# ProtocolAnalyzer.net
KiCad netlist of a schematic drawn in Altium Designer
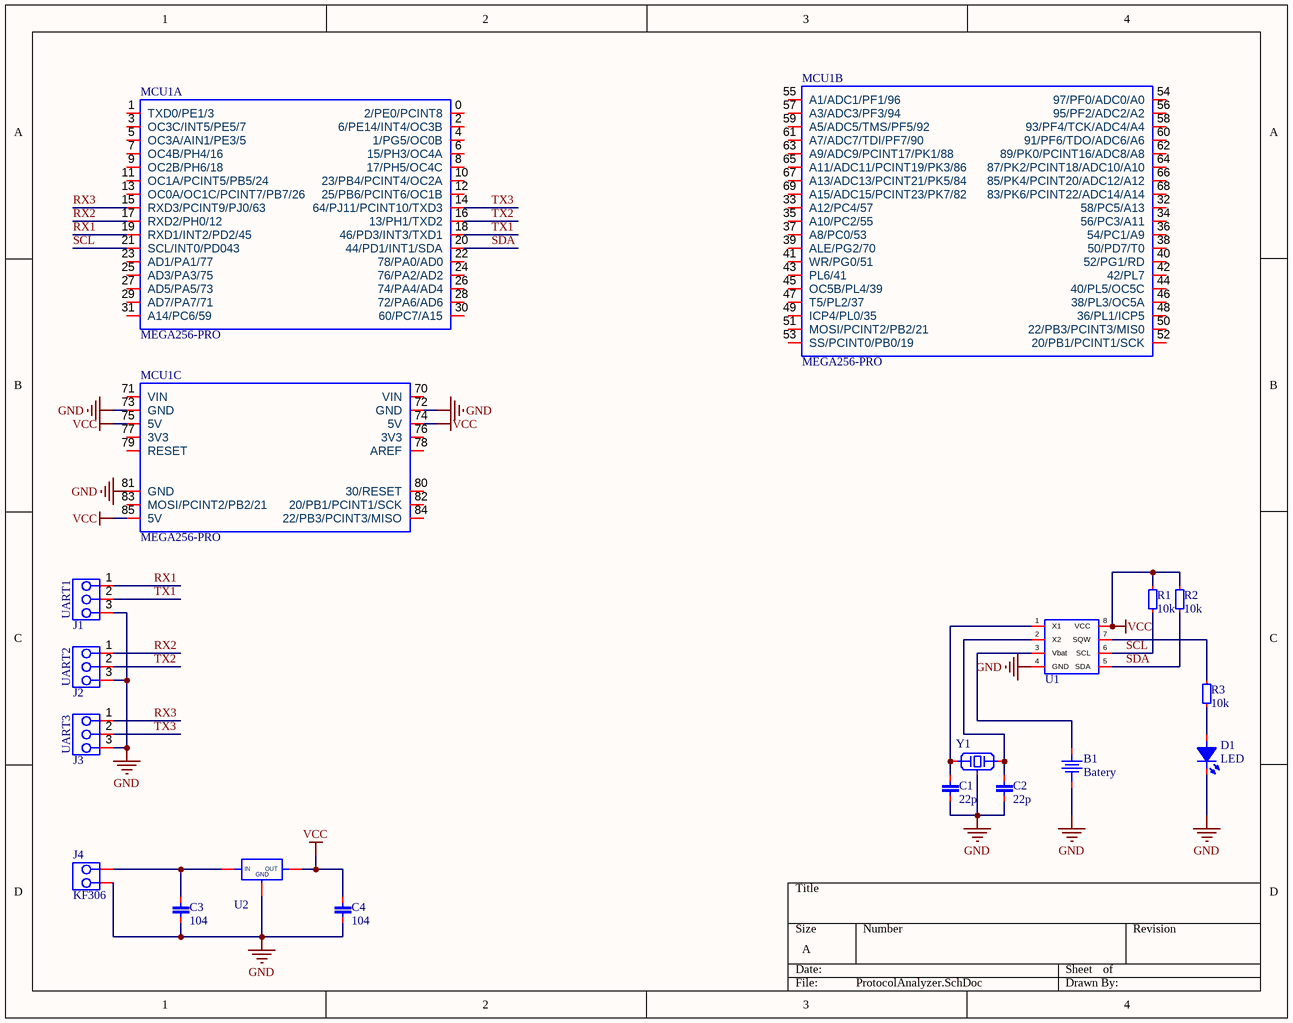
[diagram p0: ProtocolAnalyzer.SchDoc]

(export (version "E")
  (design (tool "Eeschema 10.0.6"))
  (components
    (comp (ref "B1")
      (value "Batery")
      (footprint "CR1220")
      (libsource (lib "MyAltiumLibrary") (part "Batery"))
    )
    (comp (ref "C1")
      (value "22p")
      (footprint "C0805")
      (libsource (lib "MyAltiumLibrary") (part "Capacitors(SMD)"))
    )
    (comp (ref "C2")
      (value "22p")
      (footprint "C0805")
      (libsource (lib "MyAltiumLibrary") (part "Capacitors(SMD)"))
    )
    (comp (ref "C3") (value "104") (footprint "C1206") (libsource (lib "") (part "Capacitors(SMD)_1")))
    (comp (ref "C4") (value "104") (footprint "C1206") (libsource (lib "") (part "Capacitors(SMD)_1")))
    (comp (ref "D1")
      (value "LED")
      (footprint "L0805RED")
      (libsource (lib "MyAltiumLibrary") (part "LED0805"))
    )
    (comp (ref "J1")
      (value "UART1")
      (footprint "JST - XH - Thru (R) - 3Pin - 2.54mm")
      (libsource (lib "MyAltiumLibrary") (part "JST - XH - Thru (R) - 3Pin - 2.54mm"))
    )
    (comp (ref "J2")
      (value "UART2")
      (footprint "JST - XH - Thru (R) - 3Pin - 2.54mm")
      (libsource (lib "MyAltiumLibrary") (part "JST - XH - Thru (R) - 3Pin - 2.54mm"))
    )
    (comp (ref "J3")
      (value "UART3")
      (footprint "JST - XH - Thru (R) - 3Pin - 2.54mm")
      (libsource (lib "MyAltiumLibrary") (part "JST - XH - Thru (R) - 3Pin - 2.54mm"))
    )
    (comp (ref "J4")
      (value "KF306")
      (footprint "DG306-5.0-02P-12-00AH")
      (libsource (lib "MyAltiumLibrary") (part "DG306-5.0-02P-12-00AH"))
    )
    (comp (ref "MCU1")
      (value "MEGA256-PRO")
      (footprint "MEGA2560-PRO")
      (libsource (lib "MyAltiumLibrary") (part "Arduino Mega 2560 Pro"))
    )
    (comp (ref "R1")
      (value "10k")
      (footprint "R0805")
      (libsource (lib "MyAltiumLibrary") (part "Resistors-SMD"))
    )
    (comp (ref "R2")
      (value "10k")
      (footprint "R0805")
      (libsource (lib "MyAltiumLibrary") (part "Resistors-SMD"))
    )
    (comp (ref "R3")
      (value "10k")
      (footprint "R0805")
      (libsource (lib "MyAltiumLibrary") (part "Resistors-SMD"))
    )
    (comp (ref "U1")
      (value "RealTime")
      (footprint "SOIC08_1.27_6.0")
      (libsource (lib "MyAltiumLibrary") (part "RealTime-DS1307"))
    )
    (comp (ref "U2")
      (value "LM7805")
      (footprint "TO252-3")
      (libsource (lib "MyAltiumLibrary") (part "Ic-LM7805"))
    )
    (comp (ref "Y1")
      (value "32.768KHz")
      (footprint "DT-26")
      (libsource (lib "MyAltiumLibrary") (part "Crystal 32.768KHz"))
    )
  )
  (nets
    (net (code "1") (name "/RX1") (class "Default")
      (node (ref "J1") (pin "1") (pinfunction "1_1") (pintype "passive"))
      (node (ref "MCU1") (pin "19") (pinfunction "RXD1/INT2/PD2/45_19") (pintype "passive"))
    )
    (net (code "2") (name "/RX2") (class "Default")
      (node (ref "J2") (pin "1") (pinfunction "1_1") (pintype "passive"))
      (node (ref "MCU1") (pin "17") (pinfunction "RXD2/PH0/12_17") (pintype "passive"))
    )
    (net (code "3") (name "/RX3") (class "Default")
      (node (ref "J3") (pin "1") (pinfunction "1_1") (pintype "passive"))
      (node (ref "MCU1") (pin "15") (pinfunction "RXD3/PCINT9/PJ0/63_15") (pintype "passive"))
    )
    (net (code "4") (name "/SCL") (class "Default")
      (node (ref "MCU1") (pin "21") (pinfunction "SCL/INT0/PD043_21") (pintype "passive"))
      (node (ref "R1") (pin "1") (pinfunction "1_1") (pintype "passive"))
      (node (ref "U1") (pin "6") (pinfunction "SCL_6") (pintype "passive"))
    )
    (net (code "5") (name "/SDA") (class "Default")
      (node (ref "MCU1") (pin "20") (pinfunction "44/PD1/INT1/SDA_20") (pintype "passive"))
      (node (ref "R2") (pin "1") (pinfunction "1_1") (pintype "passive"))
      (node (ref "U1") (pin "5") (pinfunction "SDA_5") (pintype "passive"))
    )
    (net (code "6") (name "/TX1") (class "Default")
      (node (ref "J1") (pin "2") (pinfunction "2_2") (pintype "passive"))
      (node (ref "MCU1") (pin "18") (pinfunction "46/PD3/INT3/TXD1_18") (pintype "passive"))
    )
    (net (code "7") (name "/TX2") (class "Default")
      (node (ref "J2") (pin "2") (pinfunction "2_2") (pintype "passive"))
      (node (ref "MCU1") (pin "16") (pinfunction "13/PH1/TXD2_16") (pintype "passive"))
    )
    (net (code "8") (name "/TX3") (class "Default")
      (node (ref "J3") (pin "2") (pinfunction "2_2") (pintype "passive"))
      (node (ref "MCU1") (pin "14") (pinfunction "64/PJ11/PCINT10/TXD3_14") (pintype "passive"))
    )
    (net (code "9") (name "GND") (class "Default")
      (node (ref "B1") (pin "2") (pinfunction "2_2") (pintype "passive"))
      (node (ref "C1") (pin "1") (pinfunction "1_1") (pintype "passive"))
      (node (ref "C2") (pin "1") (pinfunction "1_1") (pintype "passive"))
      (node (ref "C3") (pin "2") (pinfunction "2_2") (pintype "passive"))
      (node (ref "C4") (pin "2") (pinfunction "2_2") (pintype "passive"))
      (node (ref "D1") (pin "2") (pinfunction "K_2") (pintype "passive"))
      (node (ref "J1") (pin "3") (pinfunction "3_3") (pintype "passive"))
      (node (ref "J2") (pin "3") (pinfunction "3_3") (pintype "passive"))
      (node (ref "J3") (pin "3") (pinfunction "3_3") (pintype "passive"))
      (node (ref "J4") (pin "2") (pinfunction "2_2") (pintype "passive"))
      (node (ref "MCU1") (pin "72") (pinfunction "GND_72") (pintype "passive"))
      (node (ref "MCU1") (pin "73") (pinfunction "GND_73") (pintype "passive"))
      (node (ref "MCU1") (pin "81") (pinfunction "GND_81") (pintype "passive"))
      (node (ref "U1") (pin "4") (pinfunction "GND_4") (pintype "passive"))
      (node (ref "U2") (pin "2") (pinfunction "GND_2") (pintype "passive"))
      (node (ref "Y1") (pin "3") (pinfunction "GND_3") (pintype "passive"))
    )
    (net (code "10") (name "Net-(D1-A)") (class "Default")
      (node (ref "D1") (pin "1") (pinfunction "A_1") (pintype "passive"))
      (node (ref "R3") (pin "1") (pinfunction "1_1") (pintype "passive"))
    )
    (net (code "11") (name "Net-(U1-SQW)") (class "Default")
      (node (ref "R3") (pin "2") (pinfunction "2_2") (pintype "passive"))
      (node (ref "U1") (pin "7") (pinfunction "SQW_7") (pintype "passive"))
    )
    (net (code "12") (name "Net-(U1-Vbat)") (class "Default")
      (node (ref "B1") (pin "1") (pinfunction "1_1") (pintype "passive"))
      (node (ref "U1") (pin "3") (pinfunction "Vbat_3") (pintype "passive"))
    )
    (net (code "13") (name "Net-(U1-X1)") (class "Default")
      (node (ref "C1") (pin "2") (pinfunction "2_2") (pintype "passive"))
      (node (ref "U1") (pin "1") (pinfunction "X1_1") (pintype "passive"))
      (node (ref "Y1") (pin "2") (pinfunction "2_2") (pintype "passive"))
    )
    (net (code "14") (name "Net-(U1-X2)") (class "Default")
      (node (ref "C2") (pin "2") (pinfunction "2_2") (pintype "passive"))
      (node (ref "U1") (pin "2") (pinfunction "X2_2") (pintype "passive"))
      (node (ref "Y1") (pin "1") (pinfunction "1_1") (pintype "passive"))
    )
    (net (code "15") (name "Net-(U2-IN)") (class "Default")
      (node (ref "C3") (pin "1") (pinfunction "1_1") (pintype "passive"))
      (node (ref "J4") (pin "1") (pinfunction "1_1") (pintype "passive"))
      (node (ref "U2") (pin "1") (pinfunction "IN_1") (pintype "passive"))
    )
    (net (code "16") (name "VCC") (class "Default")
      (node (ref "C4") (pin "1") (pinfunction "1_1") (pintype "passive"))
      (node (ref "MCU1") (pin "74") (pinfunction "5V_74") (pintype "passive"))
      (node (ref "MCU1") (pin "75") (pinfunction "5V_75") (pintype "passive"))
      (node (ref "MCU1") (pin "85") (pinfunction "5V_85") (pintype "passive"))
      (node (ref "R1") (pin "2") (pinfunction "2_2") (pintype "passive"))
      (node (ref "R2") (pin "2") (pinfunction "2_2") (pintype "passive"))
      (node (ref "U1") (pin "8") (pinfunction "VCC_8") (pintype "passive"))
      (node (ref "U2") (pin "3") (pinfunction "OUT_3") (pintype "passive"))
    )
    (net (code "17") (name "unconnected-(MCU1A-1{slash}PG5{slash}OC0B-Pad4)") (class "Default")
      (node (ref "MCU1") (pin "4") (pinfunction "1/PG5/OC0B_4") (pintype "passive"))
    )
    (net (code "18") (name "unconnected-(MCU1A-2{slash}PE0{slash}PCINT8-Pad0)") (class "Default")
      (node (ref "MCU1") (pin "0") (pinfunction "2/PE0/PCINT8_0") (pintype "passive"))
    )
    (net (code "19") (name "unconnected-(MCU1A-6{slash}PE14{slash}INT4{slash}OC3B-Pad2)") (class "Default")
      (node (ref "MCU1") (pin "2") (pinfunction "6/PE14/INT4/OC3B_2") (pintype "passive"))
    )
    (net (code "20") (name "unconnected-(MCU1A-15{slash}PH3{slash}OC4A-Pad6)") (class "Default")
      (node (ref "MCU1") (pin "6") (pinfunction "15/PH3/OC4A_6") (pintype "passive"))
    )
    (net (code "21") (name "unconnected-(MCU1A-17{slash}PH5{slash}OC4C-Pad8)") (class "Default")
      (node (ref "MCU1") (pin "8") (pinfunction "17/PH5/OC4C_8") (pintype "passive"))
    )
    (net (code "22") (name "unconnected-(MCU1A-23{slash}PB4{slash}PCINT4{slash}OC2A-Pad10)") (class "Default")
      (node (ref "MCU1") (pin "10") (pinfunction "23/PB4/PCINT4/OC2A_10") (pintype "passive"))
    )
    (net (code "23") (name "unconnected-(MCU1A-25{slash}PB6{slash}PCINT6{slash}OC1B-Pad12)") (class "Default")
      (node (ref "MCU1") (pin "12") (pinfunction "25/PB6/PCINT6/OC1B_12") (pintype "passive"))
    )
    (net (code "24") (name "unconnected-(MCU1A-60{slash}PC7{slash}A15-Pad30)") (class "Default")
      (node (ref "MCU1") (pin "30") (pinfunction "60/PC7/A15_30") (pintype "passive"))
    )
    (net (code "25") (name "unconnected-(MCU1A-72{slash}PA6{slash}AD6-Pad28)") (class "Default")
      (node (ref "MCU1") (pin "28") (pinfunction "72/PA6/AD6_28") (pintype "passive"))
    )
    (net (code "26") (name "unconnected-(MCU1A-74{slash}PA4{slash}AD4-Pad26)") (class "Default")
      (node (ref "MCU1") (pin "26") (pinfunction "74/PA4/AD4_26") (pintype "passive"))
    )
    (net (code "27") (name "unconnected-(MCU1A-76{slash}PA2{slash}AD2-Pad24)") (class "Default")
      (node (ref "MCU1") (pin "24") (pinfunction "76/PA2/AD2_24") (pintype "passive"))
    )
    (net (code "28") (name "unconnected-(MCU1A-78{slash}PA0{slash}AD0-Pad22)") (class "Default")
      (node (ref "MCU1") (pin "22") (pinfunction "78/PA0/AD0_22") (pintype "passive"))
    )
    (net (code "29") (name "unconnected-(MCU1A-A14{slash}PC6{slash}59-Pad31)") (class "Default")
      (node (ref "MCU1") (pin "31") (pinfunction "A14/PC6/59_31") (pintype "passive"))
    )
    (net (code "30") (name "unconnected-(MCU1A-AD1{slash}PA1{slash}77-Pad23)") (class "Default")
      (node (ref "MCU1") (pin "23") (pinfunction "AD1/PA1/77_23") (pintype "passive"))
    )
    (net (code "31") (name "unconnected-(MCU1A-AD3{slash}PA3{slash}75-Pad25)") (class "Default")
      (node (ref "MCU1") (pin "25") (pinfunction "AD3/PA3/75_25") (pintype "passive"))
    )
    (net (code "32") (name "unconnected-(MCU1A-AD5{slash}PA5{slash}73-Pad27)") (class "Default")
      (node (ref "MCU1") (pin "27") (pinfunction "AD5/PA5/73_27") (pintype "passive"))
    )
    (net (code "33") (name "unconnected-(MCU1A-AD7{slash}PA7{slash}71-Pad29)") (class "Default")
      (node (ref "MCU1") (pin "29") (pinfunction "AD7/PA7/71_29") (pintype "passive"))
    )
    (net (code "34") (name "unconnected-(MCU1A-OC0A{slash}OC1C{slash}PCINT7{slash}PB7{slash}26-Pad13)") (class "Default")
      (node (ref "MCU1") (pin "13") (pinfunction "OC0A/OC1C/PCINT7/PB7/26_13") (pintype "passive"))
    )
    (net (code "35") (name "unconnected-(MCU1A-OC1A{slash}PCINT5{slash}PB5{slash}24-Pad11)") (class "Default")
      (node (ref "MCU1") (pin "11") (pinfunction "OC1A/PCINT5/PB5/24_11") (pintype "passive"))
    )
    (net (code "36") (name "unconnected-(MCU1A-OC2B{slash}PH6{slash}18-Pad9)") (class "Default")
      (node (ref "MCU1") (pin "9") (pinfunction "OC2B/PH6/18_9") (pintype "passive"))
    )
    (net (code "37") (name "unconnected-(MCU1A-OC3A{slash}AIN1{slash}PE3{slash}5-Pad5)") (class "Default")
      (node (ref "MCU1") (pin "5") (pinfunction "OC3A/AIN1/PE3/5_5") (pintype "passive"))
    )
    (net (code "38") (name "unconnected-(MCU1A-OC3C{slash}INT5{slash}PE5{slash}7-Pad3)") (class "Default")
      (node (ref "MCU1") (pin "3") (pinfunction "OC3C/INT5/PE5/7_3") (pintype "passive"))
    )
    (net (code "39") (name "unconnected-(MCU1A-OC4B{slash}PH4{slash}16-Pad7)") (class "Default")
      (node (ref "MCU1") (pin "7") (pinfunction "OC4B/PH4/16_7") (pintype "passive"))
    )
    (net (code "40") (name "unconnected-(MCU1A-TXD0{slash}PE1{slash}3-Pad1)") (class "Default")
      (node (ref "MCU1") (pin "1") (pinfunction "TXD0/PE1/3_1") (pintype "passive"))
    )
    (net (code "41") (name "unconnected-(MCU1B-20{slash}PB1{slash}PCINT1{slash}SCK-Pad52)") (class "Default")
      (node (ref "MCU1") (pin "52") (pinfunction "20/PB1/PCINT1/SCK_52") (pintype "passive"))
    )
    (net (code "42") (name "unconnected-(MCU1B-22{slash}PB3{slash}PCINT3{slash}MIS0-Pad50)") (class "Default")
      (node (ref "MCU1") (pin "50") (pinfunction "22/PB3/PCINT3/MIS0_50") (pintype "passive"))
    )
    (net (code "43") (name "unconnected-(MCU1B-36{slash}PL1{slash}ICP5-Pad48)") (class "Default")
      (node (ref "MCU1") (pin "48") (pinfunction "36/PL1/ICP5_48") (pintype "passive"))
    )
    (net (code "44") (name "unconnected-(MCU1B-38{slash}PL3{slash}OC5A-Pad46)") (class "Default")
      (node (ref "MCU1") (pin "46") (pinfunction "38/PL3/OC5A_46") (pintype "passive"))
    )
    (net (code "45") (name "unconnected-(MCU1B-40{slash}PL5{slash}OC5C-Pad44)") (class "Default")
      (node (ref "MCU1") (pin "44") (pinfunction "40/PL5/OC5C_44") (pintype "passive"))
    )
    (net (code "46") (name "unconnected-(MCU1B-42{slash}PL7-Pad42)") (class "Default")
      (node (ref "MCU1") (pin "42") (pinfunction "42/PL7_42") (pintype "passive"))
    )
    (net (code "47") (name "unconnected-(MCU1B-50{slash}PD7{slash}T0-Pad38)") (class "Default")
      (node (ref "MCU1") (pin "38") (pinfunction "50/PD7/T0_38") (pintype "passive"))
    )
    (net (code "48") (name "unconnected-(MCU1B-52{slash}PG1{slash}RD-Pad40)") (class "Default")
      (node (ref "MCU1") (pin "40") (pinfunction "52/PG1/RD_40") (pintype "passive"))
    )
    (net (code "49") (name "unconnected-(MCU1B-54{slash}PC1{slash}A9-Pad36)") (class "Default")
      (node (ref "MCU1") (pin "36") (pinfunction "54/PC1/A9_36") (pintype "passive"))
    )
    (net (code "50") (name "unconnected-(MCU1B-56{slash}PC3{slash}A11-Pad34)") (class "Default")
      (node (ref "MCU1") (pin "34") (pinfunction "56/PC3/A11_34") (pintype "passive"))
    )
    (net (code "51") (name "unconnected-(MCU1B-58{slash}PC5{slash}A13-Pad32)") (class "Default")
      (node (ref "MCU1") (pin "32") (pinfunction "58/PC5/A13_32") (pintype "passive"))
    )
    (net (code "52") (name "unconnected-(MCU1B-83{slash}PK6{slash}PCINT22{slash}ADC14{slash}A14-Pad68)") (class "Default")
      (node (ref "MCU1") (pin "68") (pinfunction "83/PK6/PCINT22/ADC14/A14_68") (pintype "passive"))
    )
    (net (code "53") (name "unconnected-(MCU1B-85{slash}PK4{slash}PCINT20{slash}ADC12{slash}A12-Pad66)") (class "Default")
      (node (ref "MCU1") (pin "66") (pinfunction "85/PK4/PCINT20/ADC12/A12_66") (pintype "passive"))
    )
    (net (code "54") (name "unconnected-(MCU1B-87{slash}PK2{slash}PCINT18{slash}ADC10{slash}A10-Pad64)") (class "Default")
      (node (ref "MCU1") (pin "64") (pinfunction "87/PK2/PCINT18/ADC10/A10_64") (pintype "passive"))
    )
    (net (code "55") (name "unconnected-(MCU1B-89{slash}PK0{slash}PCINT16{slash}ADC8{slash}A8-Pad62)") (class "Default")
      (node (ref "MCU1") (pin "62") (pinfunction "89/PK0/PCINT16/ADC8/A8_62") (pintype "passive"))
    )
    (net (code "56") (name "unconnected-(MCU1B-91{slash}PF6{slash}TDO{slash}ADC6{slash}A6-Pad60)") (class "Default")
      (node (ref "MCU1") (pin "60") (pinfunction "91/PF6/TDO/ADC6/A6_60") (pintype "passive"))
    )
    (net (code "57") (name "unconnected-(MCU1B-93{slash}PF4{slash}TCK{slash}ADC4{slash}A4-Pad58)") (class "Default")
      (node (ref "MCU1") (pin "58") (pinfunction "93/PF4/TCK/ADC4/A4_58") (pintype "passive"))
    )
    (net (code "58") (name "unconnected-(MCU1B-95{slash}PF2{slash}ADC2{slash}A2-Pad56)") (class "Default")
      (node (ref "MCU1") (pin "56") (pinfunction "95/PF2/ADC2/A2_56") (pintype "passive"))
    )
    (net (code "59") (name "unconnected-(MCU1B-97{slash}PF0{slash}ADC0{slash}A0-Pad54)") (class "Default")
      (node (ref "MCU1") (pin "54") (pinfunction "97/PF0/ADC0/A0_54") (pintype "passive"))
    )
    (net (code "60") (name "unconnected-(MCU1B-A1{slash}ADC1{slash}PF1{slash}96-Pad55)") (class "Default")
      (node (ref "MCU1") (pin "55") (pinfunction "A1/ADC1/PF1/96_55") (pintype "passive"))
    )
    (net (code "61") (name "unconnected-(MCU1B-A3{slash}ADC3{slash}PF3{slash}94-Pad57)") (class "Default")
      (node (ref "MCU1") (pin "57") (pinfunction "A3/ADC3/PF3/94_57") (pintype "passive"))
    )
    (net (code "62") (name "unconnected-(MCU1B-A5{slash}ADC5{slash}TMS{slash}PF5{slash}92-Pad59)") (class "Default")
      (node (ref "MCU1") (pin "59") (pinfunction "A5/ADC5/TMS/PF5/92_59") (pintype "passive"))
    )
    (net (code "63") (name "unconnected-(MCU1B-A7{slash}ADC7{slash}TDI{slash}PF7{slash}90-Pad61)") (class "Default")
      (node (ref "MCU1") (pin "61") (pinfunction "A7/ADC7/TDI/PF7/90_61") (pintype "passive"))
    )
    (net (code "64") (name "unconnected-(MCU1B-A8{slash}PC0{slash}53-Pad37)") (class "Default")
      (node (ref "MCU1") (pin "37") (pinfunction "A8/PC0/53_37") (pintype "passive"))
    )
    (net (code "65") (name "unconnected-(MCU1B-A9{slash}ADC9{slash}PCINT17{slash}PK1{slash}88-Pad63)") (class "Default")
      (node (ref "MCU1") (pin "63") (pinfunction "A9/ADC9/PCINT17/PK1/88_63") (pintype "passive"))
    )
    (net (code "66") (name "unconnected-(MCU1B-A10{slash}PC2{slash}55-Pad35)") (class "Default")
      (node (ref "MCU1") (pin "35") (pinfunction "A10/PC2/55_35") (pintype "passive"))
    )
    (net (code "67") (name "unconnected-(MCU1B-A11{slash}ADC11{slash}PCINT19{slash}PK3{slash}86-Pad65)") (class "Default")
      (node (ref "MCU1") (pin "65") (pinfunction "A11/ADC11/PCINT19/PK3/86_65") (pintype "passive"))
    )
    (net (code "68") (name "unconnected-(MCU1B-A12{slash}PC4{slash}57-Pad33)") (class "Default")
      (node (ref "MCU1") (pin "33") (pinfunction "A12/PC4/57_33") (pintype "passive"))
    )
    (net (code "69") (name "unconnected-(MCU1B-A13{slash}ADC13{slash}PCINT21{slash}PK5{slash}84-Pad67)") (class "Default")
      (node (ref "MCU1") (pin "67") (pinfunction "A13/ADC13/PCINT21/PK5/84_67") (pintype "passive"))
    )
    (net (code "70") (name "unconnected-(MCU1B-A15{slash}ADC15{slash}PCINT23{slash}PK7{slash}82-Pad69)") (class "Default")
      (node (ref "MCU1") (pin "69") (pinfunction "A15/ADC15/PCINT23/PK7/82_69") (pintype "passive"))
    )
    (net (code "71") (name "unconnected-(MCU1B-ALE{slash}PG2{slash}70-Pad39)") (class "Default")
      (node (ref "MCU1") (pin "39") (pinfunction "ALE/PG2/70_39") (pintype "passive"))
    )
    (net (code "72") (name "unconnected-(MCU1B-ICP4{slash}PL0{slash}35-Pad49)") (class "Default")
      (node (ref "MCU1") (pin "49") (pinfunction "ICP4/PL0/35_49") (pintype "passive"))
    )
    (net (code "73") (name "unconnected-(MCU1B-MOSI{slash}PCINT2{slash}PB2{slash}21-Pad51)") (class "Default")
      (node (ref "MCU1") (pin "51") (pinfunction "MOSI/PCINT2/PB2/21_51") (pintype "passive"))
    )
    (net (code "74") (name "unconnected-(MCU1B-OC5B{slash}PL4{slash}39-Pad45)") (class "Default")
      (node (ref "MCU1") (pin "45") (pinfunction "OC5B/PL4/39_45") (pintype "passive"))
    )
    (net (code "75") (name "unconnected-(MCU1B-PL6{slash}41-Pad43)") (class "Default")
      (node (ref "MCU1") (pin "43") (pinfunction "PL6/41_43") (pintype "passive"))
    )
    (net (code "76") (name "unconnected-(MCU1B-SS{slash}PCINT0{slash}PB0{slash}19-Pad53)") (class "Default")
      (node (ref "MCU1") (pin "53") (pinfunction "SS/PCINT0/PB0/19_53") (pintype "passive"))
    )
    (net (code "77") (name "unconnected-(MCU1B-T5{slash}PL2{slash}37-Pad47)") (class "Default")
      (node (ref "MCU1") (pin "47") (pinfunction "T5/PL2/37_47") (pintype "passive"))
    )
    (net (code "78") (name "unconnected-(MCU1B-WR{slash}PG0{slash}51-Pad41)") (class "Default")
      (node (ref "MCU1") (pin "41") (pinfunction "WR/PG0/51_41") (pintype "passive"))
    )
    (net (code "79") (name "unconnected-(MCU1C-3V3-Pad76)") (class "Default")
      (node (ref "MCU1") (pin "76") (pinfunction "3V3_76") (pintype "passive"))
    )
    (net (code "80") (name "unconnected-(MCU1C-3V3-Pad77)") (class "Default")
      (node (ref "MCU1") (pin "77") (pinfunction "3V3_77") (pintype "passive"))
    )
    (net (code "81") (name "unconnected-(MCU1C-20{slash}PB1{slash}PCINT1{slash}SCK-Pad82)") (class "Default")
      (node (ref "MCU1") (pin "82") (pinfunction "20/PB1/PCINT1/SCK_82") (pintype "passive"))
    )
    (net (code "82") (name "unconnected-(MCU1C-22{slash}PB3{slash}PCINT3{slash}MISO-Pad84)") (class "Default")
      (node (ref "MCU1") (pin "84") (pinfunction "22/PB3/PCINT3/MISO_84") (pintype "passive"))
    )
    (net (code "83") (name "unconnected-(MCU1C-30{slash}RESET-Pad80)") (class "Default")
      (node (ref "MCU1") (pin "80") (pinfunction "30/RESET_80") (pintype "passive"))
    )
    (net (code "84") (name "unconnected-(MCU1C-AREF-Pad78)") (class "Default")
      (node (ref "MCU1") (pin "78") (pinfunction "AREF_78") (pintype "passive"))
    )
    (net (code "85") (name "unconnected-(MCU1C-MOSI{slash}PCINT2{slash}PB2{slash}21-Pad83)") (class "Default")
      (node (ref "MCU1") (pin "83") (pinfunction "MOSI/PCINT2/PB2/21_83") (pintype "passive"))
    )
    (net (code "86") (name "unconnected-(MCU1C-RESET-Pad79)") (class "Default")
      (node (ref "MCU1") (pin "79") (pinfunction "RESET_79") (pintype "passive"))
    )
    (net (code "87") (name "unconnected-(MCU1C-VIN-Pad70)") (class "Default")
      (node (ref "MCU1") (pin "70") (pinfunction "VIN_70") (pintype "passive"))
    )
    (net (code "88") (name "unconnected-(MCU1C-VIN-Pad71)") (class "Default")
      (node (ref "MCU1") (pin "71") (pinfunction "VIN_71") (pintype "passive"))
    )
  )
)
